# M103B.net
KiCad netlist of a schematic drawn in EAGLE
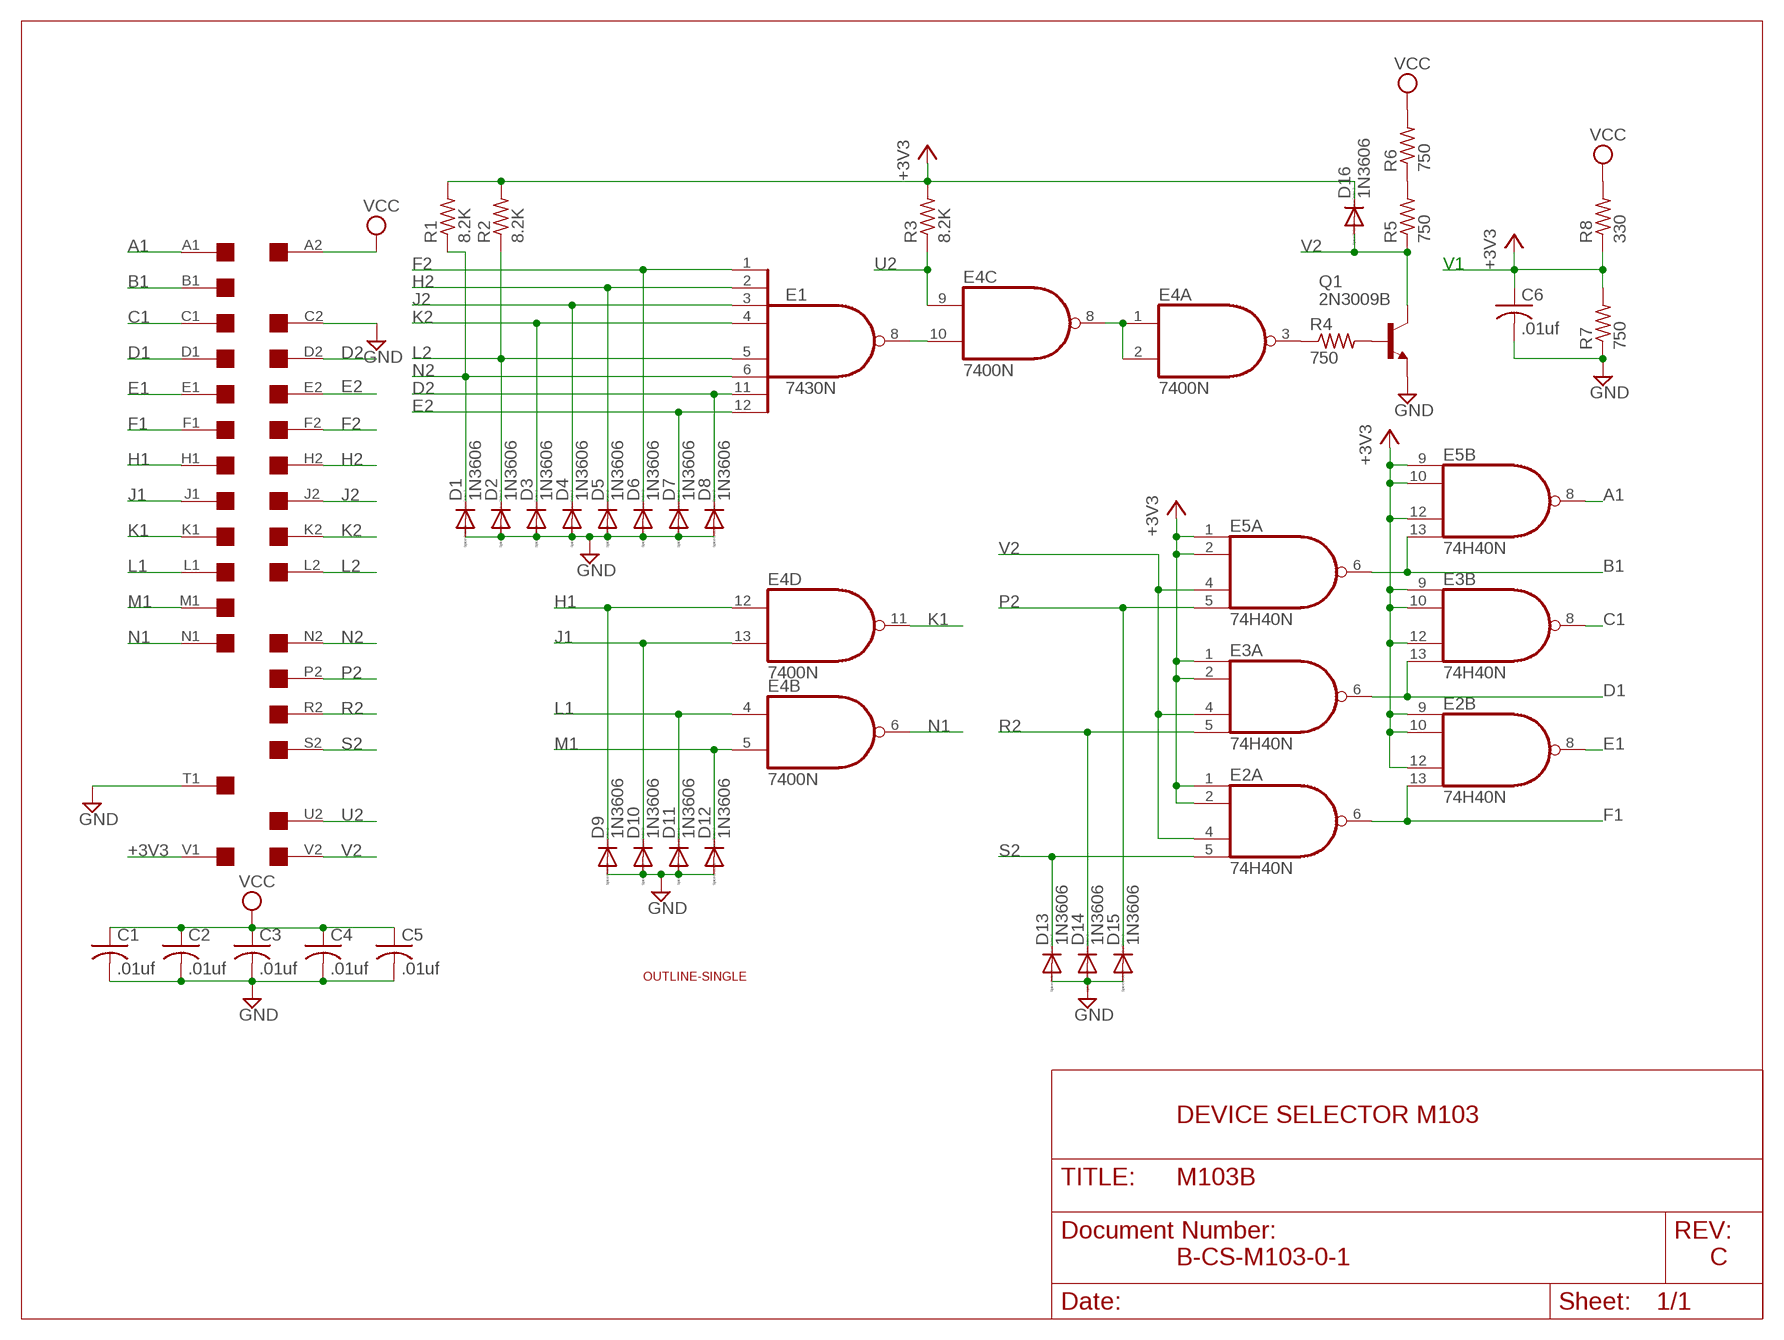
[diagram p0: schematic, sheet 1]

(export (version "E")
  (design (tool "Eeschema 10.0.6"))
  (components
    (comp (ref "C1")
      (value ".01uf")
      (footprint "eagle-import:C050-025X075")
      (libsource (lib "eagle-import") (part "C-US050-025X075"))
    )
    (comp (ref "C2")
      (value ".01uf")
      (footprint "eagle-import:C050-025X075")
      (libsource (lib "eagle-import") (part "C-US050-025X075"))
    )
    (comp (ref "C3")
      (value ".01uf")
      (footprint "eagle-import:C050-025X075")
      (libsource (lib "eagle-import") (part "C-US050-025X075"))
    )
    (comp (ref "C4")
      (value ".01uf")
      (footprint "eagle-import:C050-025X075")
      (libsource (lib "eagle-import") (part "C-US050-025X075"))
    )
    (comp (ref "C5")
      (value ".01uf")
      (footprint "eagle-import:C050-025X075")
      (libsource (lib "eagle-import") (part "C-US050-025X075"))
    )
    (comp (ref "C6")
      (value ".01uf")
      (footprint "eagle-import:C050-025X075")
      (libsource (lib "eagle-import") (part "C-US050-025X075"))
    )
    (comp (ref "D1")
      (value "1N3606")
      (footprint "eagle-import:DO35-10")
      (libsource (lib "eagle-import") (part "1N4148DO35-10"))
    )
    (comp (ref "D2")
      (value "1N3606")
      (footprint "eagle-import:DO35-10")
      (libsource (lib "eagle-import") (part "1N4148DO35-10"))
    )
    (comp (ref "D3")
      (value "1N3606")
      (footprint "eagle-import:DO35-10")
      (libsource (lib "eagle-import") (part "1N4148DO35-10"))
    )
    (comp (ref "D4")
      (value "1N3606")
      (footprint "eagle-import:DO35-10")
      (libsource (lib "eagle-import") (part "1N4148DO35-10"))
    )
    (comp (ref "D5")
      (value "1N3606")
      (footprint "eagle-import:DO35-10")
      (libsource (lib "eagle-import") (part "1N4148DO35-10"))
    )
    (comp (ref "D6")
      (value "1N3606")
      (footprint "eagle-import:DO35-10")
      (libsource (lib "eagle-import") (part "1N4148DO35-10"))
    )
    (comp (ref "D7")
      (value "1N3606")
      (footprint "eagle-import:DO35-10")
      (libsource (lib "eagle-import") (part "1N4148DO35-10"))
    )
    (comp (ref "D8")
      (value "1N3606")
      (footprint "eagle-import:DO35-10")
      (libsource (lib "eagle-import") (part "1N4148DO35-10"))
    )
    (comp (ref "D9")
      (value "1N3606")
      (footprint "eagle-import:DO35-10")
      (libsource (lib "eagle-import") (part "1N4148DO35-10"))
    )
    (comp (ref "D10")
      (value "1N3606")
      (footprint "eagle-import:DO35-10")
      (libsource (lib "eagle-import") (part "1N4148DO35-10"))
    )
    (comp (ref "D11")
      (value "1N3606")
      (footprint "eagle-import:DO35-10")
      (libsource (lib "eagle-import") (part "1N4148DO35-10"))
    )
    (comp (ref "D12")
      (value "1N3606")
      (footprint "eagle-import:DO35-10")
      (libsource (lib "eagle-import") (part "1N4148DO35-10"))
    )
    (comp (ref "D13")
      (value "1N3606")
      (footprint "eagle-import:DO35-10")
      (libsource (lib "eagle-import") (part "1N4148DO35-10"))
    )
    (comp (ref "D14")
      (value "1N3606")
      (footprint "eagle-import:DO35-10")
      (libsource (lib "eagle-import") (part "1N4148DO35-10"))
    )
    (comp (ref "D15")
      (value "1N3606")
      (footprint "eagle-import:DO35-10")
      (libsource (lib "eagle-import") (part "1N4148DO35-10"))
    )
    (comp (ref "D16")
      (value "1N3606")
      (footprint "eagle-import:DO35-10")
      (libsource (lib "eagle-import") (part "1N4148DO35-10"))
    )
    (comp (ref "E1")
      (value "7430N")
      (footprint "eagle-import:DIL14")
      (libsource (lib "eagle-import") (part "7430N"))
    )
    (comp (ref "E2")
      (value "74H40N")
      (footprint "eagle-import:DIL14")
      (libsource (lib "eagle-import") (part "7420NS"))
    )
    (comp (ref "E3")
      (value "74H40N")
      (footprint "eagle-import:DIL14")
      (libsource (lib "eagle-import") (part "7420NS"))
    )
    (comp (ref "E4")
      (value "7400N")
      (footprint "eagle-import:DIL14")
      (libsource (lib "eagle-import") (part "7400N"))
    )
    (comp (ref "E5")
      (value "74H40N")
      (footprint "eagle-import:DIL14")
      (libsource (lib "eagle-import") (part "7420NS"))
    )
    (comp (ref "Q1")
      (value "2N3009B")
      (footprint "eagle-import:TO39")
      (libsource (lib "eagle-import") (part "-NPN-TO39-EBC2N1613"))
    )
    (comp (ref "R1")
      (value "8.2K")
      (footprint "eagle-import:0207_10")
      (libsource (lib "eagle-import") (part "R-US_0207/10"))
    )
    (comp (ref "R2")
      (value "8.2K")
      (footprint "eagle-import:0207_10")
      (libsource (lib "eagle-import") (part "R-US_0207/10"))
    )
    (comp (ref "R3")
      (value "8.2K")
      (footprint "eagle-import:0207_10")
      (libsource (lib "eagle-import") (part "R-US_0207/10"))
    )
    (comp (ref "R4")
      (value "750")
      (footprint "eagle-import:0207_10")
      (libsource (lib "eagle-import") (part "R-US_0207/10"))
    )
    (comp (ref "R5")
      (value "750")
      (footprint "eagle-import:0207_10")
      (libsource (lib "eagle-import") (part "R-US_0207/10"))
    )
    (comp (ref "R6")
      (value "750")
      (footprint "eagle-import:0207_10")
      (libsource (lib "eagle-import") (part "R-US_0207/10"))
    )
    (comp (ref "R7")
      (value "750")
      (footprint "eagle-import:0207_10")
      (libsource (lib "eagle-import") (part "R-US_0207/10"))
    )
    (comp (ref "R8")
      (value "330")
      (footprint "eagle-import:0207_10")
      (libsource (lib "eagle-import") (part "R-US_0207/10"))
    )
    (comp (ref "U$8")
      (value "SINGLE")
      (footprint "eagle-import:EDGE-CON2")
      (libsource (lib "eagle-import") (part "SINGLE"))
    )
    (comp (ref "U$9")
      (value "OUTLINE-SINGLE")
      (footprint "eagle-import:SINGLE")
      (libsource (lib "eagle-import") (part "OUTLINE-SINGLE"))
    )
  )
  (nets
    (net (code "1") (name "+3V3") (class "Default")
      (node (ref "C6") (pin "1") (pinfunction "1_1") (pintype "passive"))
      (node (ref "D16") (pin "C") (pinfunction "C_C") (pintype "passive"))
      (node (ref "E2") (pin "1") (pinfunction "I0_1") (pintype "input"))
      (node (ref "E2") (pin "10") (pinfunction "I1_10") (pintype "input"))
      (node (ref "E2") (pin "12") (pinfunction "I2_12") (pintype "input"))
      (node (ref "E2") (pin "2") (pinfunction "I1_2") (pintype "input"))
      (node (ref "E2") (pin "9") (pinfunction "I0_9") (pintype "input"))
      (node (ref "E3") (pin "1") (pinfunction "I0_1") (pintype "input"))
      (node (ref "E3") (pin "10") (pinfunction "I1_10") (pintype "input"))
      (node (ref "E3") (pin "12") (pinfunction "I2_12") (pintype "input"))
      (node (ref "E3") (pin "2") (pinfunction "I1_2") (pintype "input"))
      (node (ref "E3") (pin "9") (pinfunction "I0_9") (pintype "input"))
      (node (ref "E5") (pin "1") (pinfunction "I0_1") (pintype "input"))
      (node (ref "E5") (pin "10") (pinfunction "I1_10") (pintype "input"))
      (node (ref "E5") (pin "12") (pinfunction "I2_12") (pintype "input"))
      (node (ref "E5") (pin "2") (pinfunction "I1_2") (pintype "input"))
      (node (ref "E5") (pin "9") (pinfunction "I0_9") (pintype "input"))
      (node (ref "R1") (pin "2") (pinfunction "2_2") (pintype "passive"))
      (node (ref "R2") (pin "2") (pinfunction "2_2") (pintype "passive"))
      (node (ref "R3") (pin "2") (pinfunction "2_2") (pintype "passive"))
      (node (ref "R7") (pin "2") (pinfunction "2_2") (pintype "passive"))
      (node (ref "R8") (pin "1") (pinfunction "1_1") (pintype "passive"))
      (node (ref "U$8") (pin "V1") (pinfunction "1_V1") (pintype "bidirectional"))
    )
    (net (code "2") (name "/A1") (class "Default")
      (node (ref "E5") (pin "8") (pinfunction "O_8") (pintype "output"))
      (node (ref "U$8") (pin "A1") (pinfunction "1_A1") (pintype "bidirectional"))
    )
    (net (code "3") (name "/B1") (class "Default")
      (node (ref "E5") (pin "13") (pinfunction "I3_13") (pintype "input"))
      (node (ref "E5") (pin "6") (pinfunction "O_6") (pintype "output"))
      (node (ref "U$8") (pin "B1") (pinfunction "1_B1") (pintype "bidirectional"))
    )
    (net (code "4") (name "/C1") (class "Default")
      (node (ref "E3") (pin "8") (pinfunction "O_8") (pintype "output"))
      (node (ref "U$8") (pin "C1") (pinfunction "1_C1") (pintype "bidirectional"))
    )
    (net (code "5") (name "/D1") (class "Default")
      (node (ref "E3") (pin "13") (pinfunction "I3_13") (pintype "input"))
      (node (ref "E3") (pin "6") (pinfunction "O_6") (pintype "output"))
      (node (ref "U$8") (pin "D1") (pinfunction "1_D1") (pintype "bidirectional"))
    )
    (net (code "6") (name "/D2") (class "Default")
      (node (ref "D8") (pin "C") (pinfunction "C_C") (pintype "passive"))
      (node (ref "E1") (pin "11") (pinfunction "I6_11") (pintype "input"))
      (node (ref "U$8") (pin "D2") (pinfunction "1_D2") (pintype "bidirectional"))
    )
    (net (code "7") (name "/E1") (class "Default")
      (node (ref "E2") (pin "8") (pinfunction "O_8") (pintype "output"))
      (node (ref "U$8") (pin "E1") (pinfunction "1_E1") (pintype "bidirectional"))
    )
    (net (code "8") (name "/E2") (class "Default")
      (node (ref "D7") (pin "C") (pinfunction "C_C") (pintype "passive"))
      (node (ref "E1") (pin "12") (pinfunction "I7_12") (pintype "input"))
      (node (ref "U$8") (pin "E2") (pinfunction "1_E2") (pintype "bidirectional"))
    )
    (net (code "9") (name "/F1") (class "Default")
      (node (ref "E2") (pin "13") (pinfunction "I3_13") (pintype "input"))
      (node (ref "E2") (pin "6") (pinfunction "O_6") (pintype "output"))
      (node (ref "U$8") (pin "F1") (pinfunction "1_F1") (pintype "bidirectional"))
    )
    (net (code "10") (name "/F2") (class "Default")
      (node (ref "D6") (pin "C") (pinfunction "C_C") (pintype "passive"))
      (node (ref "E1") (pin "1") (pinfunction "I0_1") (pintype "input"))
      (node (ref "U$8") (pin "F2") (pinfunction "1_F2") (pintype "bidirectional"))
    )
    (net (code "11") (name "/H1") (class "Default")
      (node (ref "D9") (pin "C") (pinfunction "C_C") (pintype "passive"))
      (node (ref "E4") (pin "12") (pinfunction "I0_12") (pintype "input"))
      (node (ref "U$8") (pin "H1") (pinfunction "1_H1") (pintype "bidirectional"))
    )
    (net (code "12") (name "/H2") (class "Default")
      (node (ref "D5") (pin "C") (pinfunction "C_C") (pintype "passive"))
      (node (ref "E1") (pin "2") (pinfunction "I1_2") (pintype "input"))
      (node (ref "U$8") (pin "H2") (pinfunction "1_H2") (pintype "bidirectional"))
    )
    (net (code "13") (name "/J1") (class "Default")
      (node (ref "D10") (pin "C") (pinfunction "C_C") (pintype "passive"))
      (node (ref "E4") (pin "13") (pinfunction "I1_13") (pintype "input"))
      (node (ref "U$8") (pin "J1") (pinfunction "1_J1") (pintype "bidirectional"))
    )
    (net (code "14") (name "/J2") (class "Default")
      (node (ref "D4") (pin "C") (pinfunction "C_C") (pintype "passive"))
      (node (ref "E1") (pin "3") (pinfunction "I2_3") (pintype "input"))
      (node (ref "U$8") (pin "J2") (pinfunction "1_J2") (pintype "bidirectional"))
    )
    (net (code "15") (name "/K1") (class "Default")
      (node (ref "E4") (pin "11") (pinfunction "O_11") (pintype "output"))
      (node (ref "U$8") (pin "K1") (pinfunction "1_K1") (pintype "bidirectional"))
    )
    (net (code "16") (name "/K2") (class "Default")
      (node (ref "D3") (pin "C") (pinfunction "C_C") (pintype "passive"))
      (node (ref "E1") (pin "4") (pinfunction "I3_4") (pintype "input"))
      (node (ref "U$8") (pin "K2") (pinfunction "1_K2") (pintype "bidirectional"))
    )
    (net (code "17") (name "/L1") (class "Default")
      (node (ref "D11") (pin "C") (pinfunction "C_C") (pintype "passive"))
      (node (ref "E4") (pin "4") (pinfunction "I0_4") (pintype "input"))
      (node (ref "U$8") (pin "L1") (pinfunction "1_L1") (pintype "bidirectional"))
    )
    (net (code "18") (name "/L2") (class "Default")
      (node (ref "D2") (pin "C") (pinfunction "C_C") (pintype "passive"))
      (node (ref "E1") (pin "5") (pinfunction "I4_5") (pintype "input"))
      (node (ref "R2") (pin "1") (pinfunction "1_1") (pintype "passive"))
      (node (ref "U$8") (pin "L2") (pinfunction "1_L2") (pintype "bidirectional"))
    )
    (net (code "19") (name "/M1") (class "Default")
      (node (ref "D12") (pin "C") (pinfunction "C_C") (pintype "passive"))
      (node (ref "E4") (pin "5") (pinfunction "I1_5") (pintype "input"))
      (node (ref "U$8") (pin "M1") (pinfunction "1_M1") (pintype "bidirectional"))
    )
    (net (code "20") (name "/N1") (class "Default")
      (node (ref "E4") (pin "6") (pinfunction "O_6") (pintype "output"))
      (node (ref "U$8") (pin "N1") (pinfunction "1_N1") (pintype "bidirectional"))
    )
    (net (code "21") (name "/N2") (class "Default")
      (node (ref "D1") (pin "C") (pinfunction "C_C") (pintype "passive"))
      (node (ref "E1") (pin "6") (pinfunction "I5_6") (pintype "input"))
      (node (ref "R1") (pin "1") (pinfunction "1_1") (pintype "passive"))
      (node (ref "U$8") (pin "N2") (pinfunction "1_N2") (pintype "bidirectional"))
    )
    (net (code "22") (name "/P2") (class "Default")
      (node (ref "D15") (pin "C") (pinfunction "C_C") (pintype "passive"))
      (node (ref "E5") (pin "5") (pinfunction "I3_5") (pintype "input"))
      (node (ref "U$8") (pin "P2") (pinfunction "1_P2") (pintype "bidirectional"))
    )
    (net (code "23") (name "/R2") (class "Default")
      (node (ref "D14") (pin "C") (pinfunction "C_C") (pintype "passive"))
      (node (ref "E3") (pin "5") (pinfunction "I3_5") (pintype "input"))
      (node (ref "U$8") (pin "R2") (pinfunction "1_R2") (pintype "bidirectional"))
    )
    (net (code "24") (name "/S2") (class "Default")
      (node (ref "D13") (pin "C") (pinfunction "C_C") (pintype "passive"))
      (node (ref "E2") (pin "5") (pinfunction "I3_5") (pintype "input"))
      (node (ref "U$8") (pin "S2") (pinfunction "1_S2") (pintype "bidirectional"))
    )
    (net (code "25") (name "/U2") (class "Default")
      (node (ref "E4") (pin "9") (pinfunction "I0_9") (pintype "input"))
      (node (ref "R3") (pin "1") (pinfunction "1_1") (pintype "passive"))
      (node (ref "U$8") (pin "U2") (pinfunction "1_U2") (pintype "bidirectional"))
    )
    (net (code "26") (name "/V2") (class "Default")
      (node (ref "D16") (pin "A") (pinfunction "A_A") (pintype "passive"))
      (node (ref "E2") (pin "4") (pinfunction "I2_4") (pintype "input"))
      (node (ref "E3") (pin "4") (pinfunction "I2_4") (pintype "input"))
      (node (ref "E5") (pin "4") (pinfunction "I2_4") (pintype "input"))
      (node (ref "Q1") (pin "3") (pinfunction "C_3") (pintype "passive"))
      (node (ref "R5") (pin "1") (pinfunction "1_1") (pintype "passive"))
      (node (ref "U$8") (pin "V2") (pinfunction "1_V2") (pintype "bidirectional"))
    )
    (net (code "27") (name "GND") (class "Default")
      (node (ref "C1") (pin "2") (pinfunction "2_2") (pintype "passive"))
      (node (ref "C2") (pin "2") (pinfunction "2_2") (pintype "passive"))
      (node (ref "C3") (pin "2") (pinfunction "2_2") (pintype "passive"))
      (node (ref "C4") (pin "2") (pinfunction "2_2") (pintype "passive"))
      (node (ref "C5") (pin "2") (pinfunction "2_2") (pintype "passive"))
      (node (ref "C6") (pin "2") (pinfunction "2_2") (pintype "passive"))
      (node (ref "D1") (pin "A") (pinfunction "A_A") (pintype "passive"))
      (node (ref "D10") (pin "A") (pinfunction "A_A") (pintype "passive"))
      (node (ref "D11") (pin "A") (pinfunction "A_A") (pintype "passive"))
      (node (ref "D12") (pin "A") (pinfunction "A_A") (pintype "passive"))
      (node (ref "D13") (pin "A") (pinfunction "A_A") (pintype "passive"))
      (node (ref "D14") (pin "A") (pinfunction "A_A") (pintype "passive"))
      (node (ref "D15") (pin "A") (pinfunction "A_A") (pintype "passive"))
      (node (ref "D2") (pin "A") (pinfunction "A_A") (pintype "passive"))
      (node (ref "D3") (pin "A") (pinfunction "A_A") (pintype "passive"))
      (node (ref "D4") (pin "A") (pinfunction "A_A") (pintype "passive"))
      (node (ref "D5") (pin "A") (pinfunction "A_A") (pintype "passive"))
      (node (ref "D6") (pin "A") (pinfunction "A_A") (pintype "passive"))
      (node (ref "D7") (pin "A") (pinfunction "A_A") (pintype "passive"))
      (node (ref "D8") (pin "A") (pinfunction "A_A") (pintype "passive"))
      (node (ref "D9") (pin "A") (pinfunction "A_A") (pintype "passive"))
      (node (ref "Q1") (pin "1") (pinfunction "E_1") (pintype "passive"))
      (node (ref "R7") (pin "1") (pinfunction "1_1") (pintype "passive"))
      (node (ref "U$8") (pin "C2") (pinfunction "1_C2") (pintype "bidirectional"))
      (node (ref "U$8") (pin "T1") (pinfunction "1_T1") (pintype "bidirectional"))
    )
    (net (code "28") (name "Net-(E1A-O)") (class "Default")
      (node (ref "E1") (pin "8") (pinfunction "O_8") (pintype "output"))
      (node (ref "E4") (pin "10") (pinfunction "I1_10") (pintype "input"))
    )
    (net (code "29") (name "Net-(E4A-I0)") (class "Default")
      (node (ref "E4") (pin "1") (pinfunction "I0_1") (pintype "input"))
      (node (ref "E4") (pin "2") (pinfunction "I1_2") (pintype "input"))
      (node (ref "E4") (pin "8") (pinfunction "O_8") (pintype "output"))
    )
    (net (code "30") (name "Net-(E4A-O)") (class "Default")
      (node (ref "E4") (pin "3") (pinfunction "O_3") (pintype "output"))
      (node (ref "R4") (pin "1") (pinfunction "1_1") (pintype "passive"))
    )
    (net (code "31") (name "Net-(Q1-B)") (class "Default")
      (node (ref "Q1") (pin "2") (pinfunction "B_2") (pintype "passive"))
      (node (ref "R4") (pin "2") (pinfunction "2_2") (pintype "passive"))
    )
    (net (code "32") (name "Net-(R5-Pad2)") (class "Default")
      (node (ref "R5") (pin "2") (pinfunction "2_2") (pintype "passive"))
      (node (ref "R6") (pin "1") (pinfunction "1_1") (pintype "passive"))
    )
    (net (code "33") (name "VCC") (class "Default")
      (node (ref "C1") (pin "1") (pinfunction "1_1") (pintype "passive"))
      (node (ref "C2") (pin "1") (pinfunction "1_1") (pintype "passive"))
      (node (ref "C3") (pin "1") (pinfunction "1_1") (pintype "passive"))
      (node (ref "C4") (pin "1") (pinfunction "1_1") (pintype "passive"))
      (node (ref "C5") (pin "1") (pinfunction "1_1") (pintype "passive"))
      (node (ref "R6") (pin "2") (pinfunction "2_2") (pintype "passive"))
      (node (ref "R8") (pin "2") (pinfunction "2_2") (pintype "passive"))
      (node (ref "U$8") (pin "A2") (pinfunction "1_A2") (pintype "bidirectional"))
    )
  )
)
